# Proiect_TSC_schema.net
KiCad netlist of a schematic drawn in EAGLE
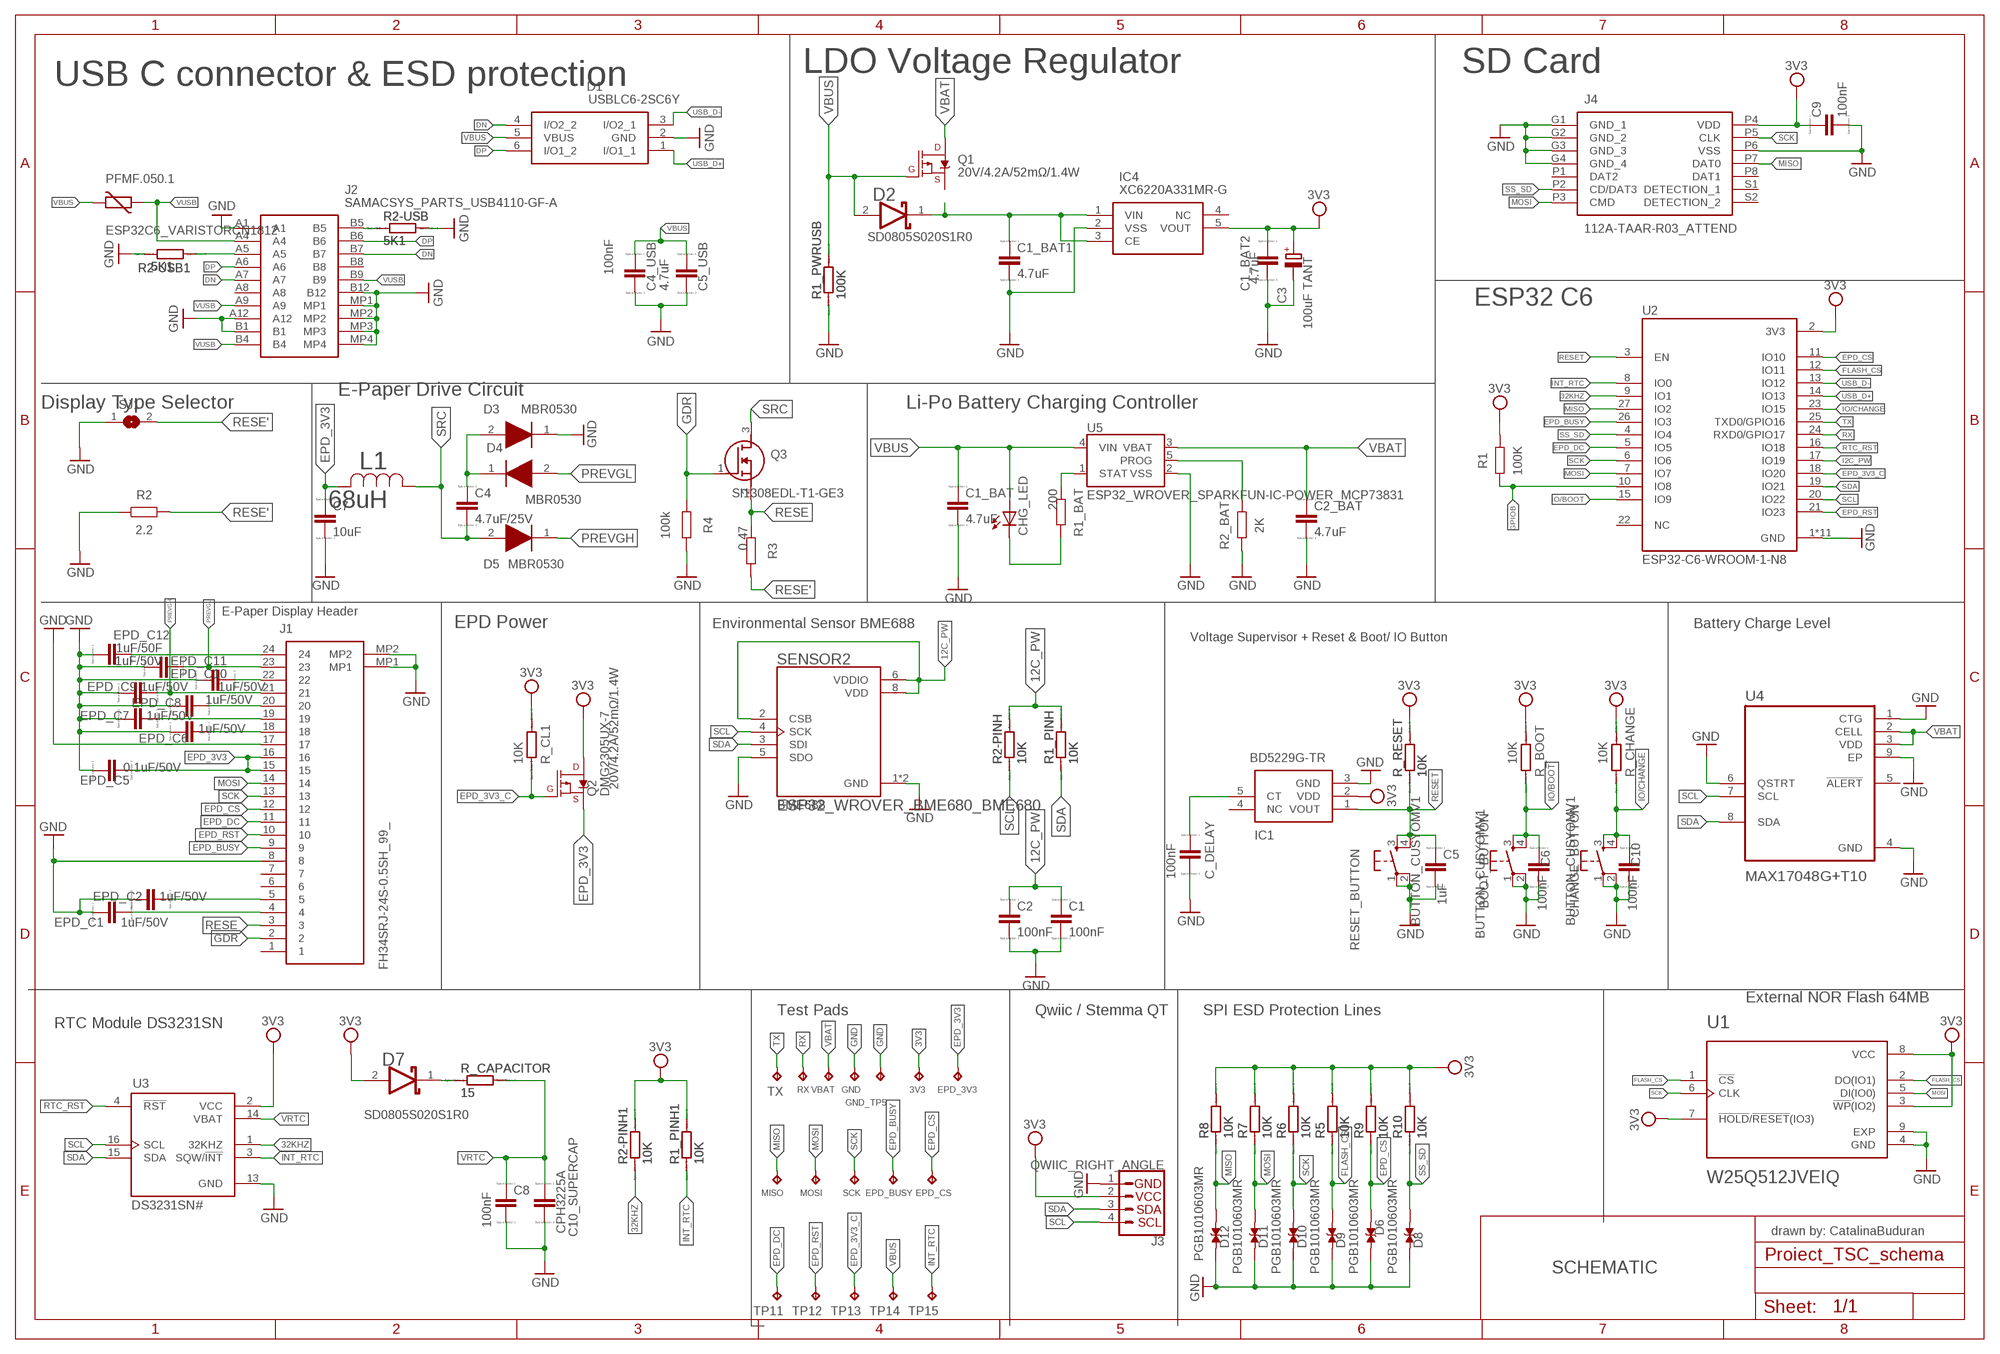
[diagram p0: schematic, sheet 1]

(export (version "E")
  (design (tool "Eeschema 10.0.6"))
  (components
    (comp (ref "3V3")
      (value "TPTP20R")
      (footprint "eagle-import:TP20R")
      (libsource (lib "eagle-import") (part "TPTP20R"))
    )
    (comp (ref "BOOT_BUTTON")
      (value "BUTTON_CUSYOMV1")
      (footprint "eagle-import:MYBUTTON")
      (libsource (lib "eagle-import") (part "BUTTON_CUSYOMV1"))
    )
    (comp (ref "C1")
      (value "100nF")
      (footprint "eagle-import:ESP32_WROVER_EAGLE-LTSPICE_C0402")
      (libsource (lib "eagle-import") (part "ESP32_WROVER_EAGLE-LTSPICE_CC0402"))
    )
    (comp (ref "C1_BAT")
      (value "4.7uF")
      (footprint "eagle-import:ESP32_WROVER_EAGLE-LTSPICE_C0402")
      (libsource (lib "eagle-import") (part "ESP32_WROVER_EAGLE-LTSPICE_CC0402"))
    )
    (comp (ref "C1_BAT1")
      (value "4.7uF")
      (footprint "eagle-import:ESP32_WROVER_EAGLE-LTSPICE_C0402")
      (libsource (lib "eagle-import") (part "ESP32_WROVER_EAGLE-LTSPICE_CC0402"))
    )
    (comp (ref "C1_BAT2")
      (value "4.7uF")
      (footprint "eagle-import:ESP32_WROVER_EAGLE-LTSPICE_C0402")
      (libsource (lib "eagle-import") (part "ESP32_WROVER_EAGLE-LTSPICE_CC0402"))
    )
    (comp (ref "C2")
      (value "100nF")
      (footprint "eagle-import:ESP32_WROVER_EAGLE-LTSPICE_C0402")
      (libsource (lib "eagle-import") (part "ESP32_WROVER_EAGLE-LTSPICE_CC0402"))
    )
    (comp (ref "C2_BAT")
      (value "4.7uF")
      (footprint "eagle-import:ESP32_WROVER_EAGLE-LTSPICE_C0402")
      (libsource (lib "eagle-import") (part "ESP32_WROVER_EAGLE-LTSPICE_CC0402"))
    )
    (comp (ref "C3")
      (value "100uF TANT")
      (footprint "eagle-import:RCL_CT3528")
      (libsource (lib "eagle-import") (part "RCL_CPOL-EUCT3528"))
    )
    (comp (ref "C4")
      (value "4.7uF/25V")
      (footprint "eagle-import:ESP32_WROVER_EAGLE-LTSPICE_C0402")
      (libsource (lib "eagle-import") (part "ESP32_WROVER_EAGLE-LTSPICE_CC0402"))
    )
    (comp (ref "C4_USB")
      (value "100nF")
      (footprint "eagle-import:ESP32_WROVER_EAGLE-LTSPICE_C0402")
      (libsource (lib "eagle-import") (part "ESP32_WROVER_EAGLE-LTSPICE_CC0402"))
    )
    (comp (ref "C5")
      (value "1uF")
      (footprint "eagle-import:EAGLE-LTSPICE_C0402")
      (libsource (lib "eagle-import") (part "EAGLE-LTSPICE_CC0402"))
    )
    (comp (ref "C5_USB")
      (value "4.7uF")
      (footprint "eagle-import:ESP32_WROVER_EAGLE-LTSPICE_C0402")
      (libsource (lib "eagle-import") (part "ESP32_WROVER_EAGLE-LTSPICE_CC0402"))
    )
    (comp (ref "C6")
      (value "100nF")
      (footprint "eagle-import:ESP32_WROVER_EAGLE-LTSPICE_C0402")
      (libsource (lib "eagle-import") (part "ESP32_WROVER_EAGLE-LTSPICE_CC0402"))
    )
    (comp (ref "C7")
      (value "10uF")
      (footprint "eagle-import:ESP32_WROVER_EAGLE-LTSPICE_C0402")
      (libsource (lib "eagle-import") (part "ESP32_WROVER_EAGLE-LTSPICE_CC0402"))
    )
    (comp (ref "C8")
      (value "100nF")
      (footprint "eagle-import:EAGLE-LTSPICE_C0402")
      (libsource (lib "eagle-import") (part "EAGLE-LTSPICE_CC0402"))
    )
    (comp (ref "C9")
      (value "100nF")
      (footprint "eagle-import:ESP32_WROVER_EAGLE-LTSPICE_C0402")
      (libsource (lib "eagle-import") (part "ESP32_WROVER_EAGLE-LTSPICE_CC0402"))
    )
    (comp (ref "C10")
      (value "100nF")
      (footprint "eagle-import:ESP32_WROVER_EAGLE-LTSPICE_C0402")
      (libsource (lib "eagle-import") (part "ESP32_WROVER_EAGLE-LTSPICE_CC0402"))
    )
    (comp (ref "C10_SUPERCAP")
      (value "CPH3225A")
      (footprint "eagle-import:EAGLE-LTSPICE_C0402")
      (libsource (lib "eagle-import") (part "EAGLE-LTSPICE_CC0402"))
    )
    (comp (ref "CHANGE_BUTTON")
      (value "BUTTON_CUSYOMV1")
      (footprint "eagle-import:MYBUTTON")
      (libsource (lib "eagle-import") (part "BUTTON_CUSYOMV1"))
    )
    (comp (ref "CHG_LED")
      (value "ADAFRUIT_LEDCHIP-LED0603")
      (footprint "eagle-import:ADAFRUIT_CHIP-LED0603")
      (libsource (lib "eagle-import") (part "ADAFRUIT_LEDCHIP-LED0603"))
    )
    (comp (ref "C_DELAY")
      (value "100nF")
      (footprint "eagle-import:ESP32_WROVER_EAGLE-LTSPICE_C0402")
      (libsource (lib "eagle-import") (part "ESP32_WROVER_EAGLE-LTSPICE_CC0402"))
    )
    (comp (ref "D1")
      (value "USBLC6-2SC6Y")
      (footprint "eagle-import:SOT95P280X145-6N")
      (fields (field (name "MF") "STMicroelectronics"))
      (libsource (lib "eagle-import") (part "USBLC6-2SC6Y"))
    )
    (comp (ref "D2")
      (value "ESP32_WROVER_AVX---SD0805S020S1R0_AVX_SD0805S020S1R0_0_0AVX_SD0805S020S1R0_0_0")
      (footprint "eagle-import:ESP32_WROVER_AVX---SD0805S020S1R0_AVX_SD0805S020S1R0_0")
      (fields
        (field (name "DIGIKEY_PART_NUMBER") "478-7800-1-ND")
        (field (name "MF") "AVX")
        (field (name "MOUSER_PART_NUMBER") "581-SD0805S020S1R0")
      )
      (libsource (lib "eagle-import") (part "ESP32_WROVER_AVX---SD0805S020S1R0_AVX_SD0805S020S1R0_0_0AVX_SD0805S020S1R0_0_0"))
    )
    (comp (ref "D3")
      (value "MBR0530")
      (footprint "eagle-import:SOD3716X135N")
      (fields (field (name "MF") "ON Semiconductor"))
      (libsource (lib "eagle-import") (part "MBR0530"))
    )
    (comp (ref "D4")
      (value "MBR0530")
      (footprint "eagle-import:SOD3716X135N")
      (fields (field (name "MF") "ON Semiconductor"))
      (libsource (lib "eagle-import") (part "MBR0530"))
    )
    (comp (ref "D5")
      (value "MBR0530")
      (footprint "eagle-import:SOD3716X135N")
      (fields (field (name "MF") "ON Semiconductor"))
      (libsource (lib "eagle-import") (part "MBR0530"))
    )
    (comp (ref "D6")
      (value "PGB1010603MR")
      (footprint "eagle-import:DIOC1608X36N")
      (fields (field (name "MF") "Littelfuse Inc."))
      (libsource (lib "eagle-import") (part "PGB1010603MR"))
    )
    (comp (ref "D7")
      (value "ESP32_WROVER_AVX---SD0805S020S1R0_AVX_SD0805S020S1R0_0_0AVX_SD0805S020S1R0_0_0")
      (footprint "eagle-import:ESP32_WROVER_AVX---SD0805S020S1R0_AVX_SD0805S020S1R0_0")
      (fields
        (field (name "DIGIKEY_PART_NUMBER") "478-7800-1-ND")
        (field (name "MF") "AVX")
        (field (name "MOUSER_PART_NUMBER") "581-SD0805S020S1R0")
      )
      (libsource (lib "eagle-import") (part "ESP32_WROVER_AVX---SD0805S020S1R0_AVX_SD0805S020S1R0_0_0AVX_SD0805S020S1R0_0_0"))
    )
    (comp (ref "D8")
      (value "PGB1010603MR")
      (footprint "eagle-import:DIOC1608X36N")
      (fields (field (name "MF") "Littelfuse Inc."))
      (libsource (lib "eagle-import") (part "PGB1010603MR"))
    )
    (comp (ref "D9")
      (value "PGB1010603MR")
      (footprint "eagle-import:DIOC1608X36N")
      (fields (field (name "MF") "Littelfuse Inc."))
      (libsource (lib "eagle-import") (part "PGB1010603MR"))
    )
    (comp (ref "D10")
      (value "PGB1010603MR")
      (footprint "eagle-import:DIOC1608X36N")
      (fields (field (name "MF") "Littelfuse Inc."))
      (libsource (lib "eagle-import") (part "PGB1010603MR"))
    )
    (comp (ref "D11")
      (value "PGB1010603MR")
      (footprint "eagle-import:DIOC1608X36N")
      (fields (field (name "MF") "Littelfuse Inc."))
      (libsource (lib "eagle-import") (part "PGB1010603MR"))
    )
    (comp (ref "D12")
      (value "PGB1010603MR")
      (footprint "eagle-import:DIOC1608X36N")
      (fields (field (name "MF") "Littelfuse Inc."))
      (libsource (lib "eagle-import") (part "PGB1010603MR"))
    )
    (comp (ref "EPD_3V3")
      (value "TPTP20R")
      (footprint "eagle-import:TP20R")
      (libsource (lib "eagle-import") (part "TPTP20R"))
    )
    (comp (ref "EPD_BUSY")
      (value "TPTP20R")
      (footprint "eagle-import:TP20R")
      (libsource (lib "eagle-import") (part "TPTP20R"))
    )
    (comp (ref "EPD_C1")
      (value "1uF/50V")
      (footprint "eagle-import:ESP32_WROVER_EAGLE-LTSPICE_C0402")
      (libsource (lib "eagle-import") (part "ESP32_WROVER_EAGLE-LTSPICE_CC0402"))
    )
    (comp (ref "EPD_C2")
      (value "1uF/50V")
      (footprint "eagle-import:ESP32_WROVER_EAGLE-LTSPICE_C0402")
      (libsource (lib "eagle-import") (part "ESP32_WROVER_EAGLE-LTSPICE_CC0402"))
    )
    (comp (ref "EPD_C5")
      (value "0.1uF/50V")
      (footprint "eagle-import:ESP32_WROVER_EAGLE-LTSPICE_C0402")
      (libsource (lib "eagle-import") (part "ESP32_WROVER_EAGLE-LTSPICE_CC0402"))
    )
    (comp (ref "EPD_C6")
      (value "1uF/50V")
      (footprint "eagle-import:ESP32_WROVER_EAGLE-LTSPICE_C0402")
      (libsource (lib "eagle-import") (part "ESP32_WROVER_EAGLE-LTSPICE_CC0402"))
    )
    (comp (ref "EPD_C7")
      (value "1uF/50V")
      (footprint "eagle-import:ESP32_WROVER_EAGLE-LTSPICE_C0402")
      (libsource (lib "eagle-import") (part "ESP32_WROVER_EAGLE-LTSPICE_CC0402"))
    )
    (comp (ref "EPD_C8")
      (value "1uF/50V")
      (footprint "eagle-import:ESP32_WROVER_EAGLE-LTSPICE_C0402")
      (libsource (lib "eagle-import") (part "ESP32_WROVER_EAGLE-LTSPICE_CC0402"))
    )
    (comp (ref "EPD_C9")
      (value "1uF/50V")
      (footprint "eagle-import:ESP32_WROVER_EAGLE-LTSPICE_C0402")
      (libsource (lib "eagle-import") (part "ESP32_WROVER_EAGLE-LTSPICE_CC0402"))
    )
    (comp (ref "EPD_C10")
      (value "1uF/50V")
      (footprint "eagle-import:ESP32_WROVER_EAGLE-LTSPICE_C0402")
      (libsource (lib "eagle-import") (part "ESP32_WROVER_EAGLE-LTSPICE_CC0402"))
    )
    (comp (ref "EPD_C11")
      (value "1uF/50V")
      (footprint "eagle-import:ESP32_WROVER_EAGLE-LTSPICE_C0402")
      (libsource (lib "eagle-import") (part "ESP32_WROVER_EAGLE-LTSPICE_CC0402"))
    )
    (comp (ref "EPD_C12")
      (value "1uF/50F")
      (footprint "eagle-import:ESP32_WROVER_EAGLE-LTSPICE_C0402")
      (libsource (lib "eagle-import") (part "ESP32_WROVER_EAGLE-LTSPICE_CC0402"))
    )
    (comp (ref "EPD_CS")
      (value "TPTP20R")
      (footprint "eagle-import:TP20R")
      (libsource (lib "eagle-import") (part "TPTP20R"))
    )
    (comp (ref "GND")
      (value "TPTP20R")
      (footprint "eagle-import:TP20R")
      (libsource (lib "eagle-import") (part "TPTP20R"))
    )
    (comp (ref "GND_TP5")
      (value "TPTP20R")
      (footprint "eagle-import:TP20R")
      (libsource (lib "eagle-import") (part "TPTP20R"))
    )
    (comp (ref "IC1")
      (value "BD5229G-TR")
      (footprint "eagle-import:SOT95P280X125-5N")
      (fields (field (name "MOUSER_PART_NUMBER") "755-BD5229G-TR"))
      (libsource (lib "eagle-import") (part "BD5229G-TR"))
    )
    (comp (ref "IC4")
      (value "XC6220A331MR-G")
      (footprint "eagle-import:SOT95P280X120-5N")
      (fields (field (name "MOUSER_PART_NUMBER") "865-XC6220A331MR-G"))
      (libsource (lib "eagle-import") (part "XC6220A331MR-G"))
    )
    (comp (ref "J1")
      (value "FH34SRJ-24S-0.5SH_99_")
      (footprint "eagle-import:FH34SRJ24S05SH99")
      (fields
        (field (name "MANUFACTURER_PART_NUMBER") "FH34SRJ-24S-0.5SH(99)")
        (field (name "MOUSER_PART_NUMBER") "798-FH34SRJ24S05SH99")
      )
      (libsource (lib "eagle-import") (part "FH34SRJ-24S-0.5SH_99_"))
    )
    (comp (ref "J2")
      (value "SAMACSYS_PARTS_USB4110-GF-A")
      (footprint "eagle-import:SAMACSYS_PARTS_USB4110GFA")
      (fields
        (field (name "MANUFACTURER_PART_NUMBER") "USB4110-GF-A")
        (field (name "MOUSER_PART_NUMBER") "640-USB4110-GF-A")
      )
      (libsource (lib "eagle-import") (part "SAMACSYS_PARTS_USB4110-GF-A"))
    )
    (comp (ref "J3")
      (value "QWIIC_RIGHT_ANGLE")
      (footprint "eagle-import:JST04_1MM_RA")
      (libsource (lib "eagle-import") (part "QWIIC_CONNECTORJS-1MM"))
    )
    (comp (ref "J4")
      (value "112A-TAAR-R03_ATTEND")
      (footprint "eagle-import:112ATAARR03ATTEND")
      (fields (field (name "MANUFACTURER_PART_NUMBER") "112A-TAAR-R03 ATTEND"))
      (libsource (lib "eagle-import") (part "112A-TAAR-R03_ATTEND"))
    )
    (comp (ref "L1")
      (value "68uH")
      (footprint "eagle-import:IND_4828-WE-TPC_WRE")
      (fields
        (field (name "MANUFACTURER_PART_NUMBER") "744043680")
        (field (name "COPYRIGHT") "Copyright (C) 2024 Ultra Librarian. All rights reserved.")
      )
      (libsource (lib "eagle-import") (part "744043680IND_4828-WE-TPC_WRE"))
    )
    (comp (ref "MISO")
      (value "TPTP20R")
      (footprint "eagle-import:TP20R")
      (libsource (lib "eagle-import") (part "TPTP20R"))
    )
    (comp (ref "MOSI")
      (value "TPTP20R")
      (footprint "eagle-import:TP20R")
      (libsource (lib "eagle-import") (part "TPTP20R"))
    )
    (comp (ref "PFMF.050.1")
      (value "ESP32C6_VARISTORCN1812")
      (footprint "eagle-import:ESP32C6_VARISTOR_CT_CN1812")
      (libsource (lib "eagle-import") (part "ESP32C6_VARISTORCN1812"))
    )
    (comp (ref "Q1")
      (value "20V/4.2A/52mΩ/1.4W")
      (footprint "eagle-import:ESP32_WROVER_SPARKFUN-DISCRETESEMI_SOT23-3")
      (libsource (lib "eagle-import") (part "ESP32_WROVER_SPARKFUN-DISCRETESEMI_MOSFET_PCH-DMG2305UX-7"))
    )
    (comp (ref "Q2")
      (value "20V/4.2A/52mΩ/1.4W")
      (footprint "eagle-import:ESP32_WROVER_SPARKFUN-DISCRETESEMI_SOT23-3")
      (libsource (lib "eagle-import") (part "ESP32_WROVER_SPARKFUN-DISCRETESEMI_MOSFET_PCH-DMG2305UX-7"))
    )
    (comp (ref "Q3")
      (value "SI1308EDL-T1-GE3")
      (footprint "eagle-import:SOT65P210X110-3N")
      (fields (field (name "MF") "Vishay Siliconix"))
      (libsource (lib "eagle-import") (part "SI1308EDL-T1-GE3"))
    )
    (comp (ref "R1")
      (value "100K")
      (footprint "eagle-import:RESC1005X40")
      (libsource (lib "eagle-import") (part "RCHIP-0402(1005-METRIC)_"))
    )
    (comp (ref "R1_BAT")
      (value "200")
      (footprint "eagle-import:RESC1005X40")
      (libsource (lib "eagle-import") (part "RCHIP-0402(1005-METRIC)_"))
    )
    (comp (ref "R1_PINH")
      (value "10K")
      (footprint "eagle-import:ESP32_WROVER_EAGLE-LTSPICE_R0402")
      (libsource (lib "eagle-import") (part "ESP32_WROVER_EAGLE-LTSPICE_RR0402"))
    )
    (comp (ref "R1_PINH1")
      (value "10K")
      (footprint "eagle-import:ESP32_WROVER_EAGLE-LTSPICE_R0402")
      (libsource (lib "eagle-import") (part "ESP32_WROVER_EAGLE-LTSPICE_RR0402"))
    )
    (comp (ref "R1_PWRUSB")
      (value "100K")
      (footprint "eagle-import:ESP32_WROVER_EAGLE-LTSPICE_R0402")
      (libsource (lib "eagle-import") (part "ESP32_WROVER_EAGLE-LTSPICE_RR0402"))
    )
    (comp (ref "R2")
      (value "2.2")
      (footprint "eagle-import:RESC1005X40")
      (libsource (lib "eagle-import") (part "RCHIP-0402(1005-METRIC)_"))
    )
    (comp (ref "R2-PINH")
      (value "10K")
      (footprint "eagle-import:ESP32_WROVER_EAGLE-LTSPICE_R0402")
      (libsource (lib "eagle-import") (part "ESP32_WROVER_EAGLE-LTSPICE_RR0402"))
    )
    (comp (ref "R2-PINH1")
      (value "10K")
      (footprint "eagle-import:ESP32_WROVER_EAGLE-LTSPICE_R0402")
      (libsource (lib "eagle-import") (part "ESP32_WROVER_EAGLE-LTSPICE_RR0402"))
    )
    (comp (ref "R2-USB")
      (value "5K1")
      (footprint "eagle-import:ESP32_WROVER_EAGLE-LTSPICE_R0402")
      (libsource (lib "eagle-import") (part "ESP32_WROVER_EAGLE-LTSPICE_RR0402"))
    )
    (comp (ref "R2-USB1")
      (value "5K1")
      (footprint "eagle-import:ESP32_WROVER_EAGLE-LTSPICE_R0402")
      (libsource (lib "eagle-import") (part "ESP32_WROVER_EAGLE-LTSPICE_RR0402"))
    )
    (comp (ref "R2_BAT")
      (value "2K")
      (footprint "eagle-import:RESC1005X40")
      (libsource (lib "eagle-import") (part "RCHIP-0402(1005-METRIC)_"))
    )
    (comp (ref "R3")
      (value "0.47")
      (footprint "eagle-import:RESC1005X40")
      (libsource (lib "eagle-import") (part "RCHIP-0402(1005-METRIC)_"))
    )
    (comp (ref "R4")
      (value "100k")
      (footprint "eagle-import:RESC1005X40")
      (libsource (lib "eagle-import") (part "RCHIP-0402(1005-METRIC)_"))
    )
    (comp (ref "R5")
      (value "10K")
      (footprint "eagle-import:ESP32_WROVER_EAGLE-LTSPICE_R0402")
      (libsource (lib "eagle-import") (part "ESP32_WROVER_EAGLE-LTSPICE_RR0402"))
    )
    (comp (ref "R6")
      (value "10K")
      (footprint "eagle-import:ESP32_WROVER_EAGLE-LTSPICE_R0402")
      (libsource (lib "eagle-import") (part "ESP32_WROVER_EAGLE-LTSPICE_RR0402"))
    )
    (comp (ref "R7")
      (value "10K")
      (footprint "eagle-import:ESP32_WROVER_EAGLE-LTSPICE_R0402")
      (libsource (lib "eagle-import") (part "ESP32_WROVER_EAGLE-LTSPICE_RR0402"))
    )
    (comp (ref "R8")
      (value "10K")
      (footprint "eagle-import:ESP32_WROVER_EAGLE-LTSPICE_R0402")
      (libsource (lib "eagle-import") (part "ESP32_WROVER_EAGLE-LTSPICE_RR0402"))
    )
    (comp (ref "R9")
      (value "10K")
      (footprint "eagle-import:ESP32_WROVER_EAGLE-LTSPICE_R0402")
      (libsource (lib "eagle-import") (part "ESP32_WROVER_EAGLE-LTSPICE_RR0402"))
    )
    (comp (ref "R10")
      (value "10K")
      (footprint "eagle-import:ESP32_WROVER_EAGLE-LTSPICE_R0402")
      (libsource (lib "eagle-import") (part "ESP32_WROVER_EAGLE-LTSPICE_RR0402"))
    )
    (comp (ref "RESET_BUTTON")
      (value "BUTTON_CUSYOMV1")
      (footprint "eagle-import:MYBUTTON")
      (libsource (lib "eagle-import") (part "BUTTON_CUSYOMV1"))
    )
    (comp (ref "RX")
      (value "TPTP20R")
      (footprint "eagle-import:TP20R")
      (libsource (lib "eagle-import") (part "TPTP20R"))
    )
    (comp (ref "R_BOOT")
      (value "10K")
      (footprint "eagle-import:ESP32_WROVER_EAGLE-LTSPICE_R0402")
      (libsource (lib "eagle-import") (part "ESP32_WROVER_EAGLE-LTSPICE_RR0402"))
    )
    (comp (ref "R_CAPACITOR")
      (value "15")
      (footprint "eagle-import:ESP32_WROVER_EAGLE-LTSPICE_R0402")
      (libsource (lib "eagle-import") (part "ESP32_WROVER_EAGLE-LTSPICE_RR0402"))
    )
    (comp (ref "R_CHANGE")
      (value "10K")
      (footprint "eagle-import:ESP32_WROVER_EAGLE-LTSPICE_R0402")
      (libsource (lib "eagle-import") (part "ESP32_WROVER_EAGLE-LTSPICE_RR0402"))
    )
    (comp (ref "R_CL1")
      (value "10K")
      (footprint "eagle-import:ESP32_WROVER_EAGLE-LTSPICE_R0402")
      (libsource (lib "eagle-import") (part "ESP32_WROVER_EAGLE-LTSPICE_RR0402"))
    )
    (comp (ref "R_RESET")
      (value "10K")
      (footprint "eagle-import:ESP32_WROVER_EAGLE-LTSPICE_R0402")
      (libsource (lib "eagle-import") (part "ESP32_WROVER_EAGLE-LTSPICE_RR0402"))
    )
    (comp (ref "SCK")
      (value "TPTP20R")
      (footprint "eagle-import:TP20R")
      (libsource (lib "eagle-import") (part "TPTP20R"))
    )
    (comp (ref "SENSOR2")
      (value "ESP32_WROVER_BME680_BME680")
      (footprint "eagle-import:ESP32_WROVER_BME680_PSON80P300X300X100-8N")
      (fields (field (name "MF") "Bosch Sensortec") (field (name "MP") "BME680"))
      (libsource (lib "eagle-import") (part "ESP32_WROVER_BME680_BME680"))
    )
    (comp (ref "SJ1") (value "SJ") (footprint "eagle-import:SJ") (libsource (lib "eagle-import") (part "SJ")))
    (comp (ref "TP11")
      (value "TPTP20R")
      (footprint "eagle-import:TP20R")
      (libsource (lib "eagle-import") (part "TPTP20R"))
    )
    (comp (ref "TP12")
      (value "TPTP20R")
      (footprint "eagle-import:TP20R")
      (libsource (lib "eagle-import") (part "TPTP20R"))
    )
    (comp (ref "TP13")
      (value "TPTP20R")
      (footprint "eagle-import:TP20R")
      (libsource (lib "eagle-import") (part "TPTP20R"))
    )
    (comp (ref "TP14")
      (value "TPTP20R")
      (footprint "eagle-import:TP20R")
      (libsource (lib "eagle-import") (part "TPTP20R"))
    )
    (comp (ref "TP15")
      (value "TPTP20R")
      (footprint "eagle-import:TP20R")
      (libsource (lib "eagle-import") (part "TPTP20R"))
    )
    (comp (ref "TX")
      (value "TPTP20R")
      (footprint "eagle-import:TP20R")
      (libsource (lib "eagle-import") (part "TPTP20R"))
    )
    (comp (ref "U1")
      (value "W25Q512JVEIQ")
      (footprint "eagle-import:SON127P600X800X80-9N")
      (fields (field (name "MF") "Winbond Electronics"))
      (libsource (lib "eagle-import") (part "W25Q512JVEIQ"))
    )
    (comp (ref "U2")
      (value "ESP32-C6-WROOM-1-N8")
      (footprint "eagle-import:XCVR_ESP32-C6-WROOM-1-N8")
      (fields (field (name "MF") "Espressif Systems"))
      (libsource (lib "eagle-import") (part "ESP32-C6-WROOM-1-N8"))
    )
    (comp (ref "U3")
      (value "DS3231SN#")
      (footprint "eagle-import:SOIC127P1032X265-16N")
      (fields (field (name "MF") "Analog Devices"))
      (libsource (lib "eagle-import") (part "DS3231SN#"))
    )
    (comp (ref "U4")
      (value "MAX17048G+T10")
      (footprint "eagle-import:SON50P200X200X80-9N")
      (fields (field (name "MF") "Analog Devices"))
      (libsource (lib "eagle-import") (part "MAX17048G+T10"))
    )
    (comp (ref "U5")
      (value "ESP32_WROVER_SPARKFUN-IC-POWER_MCP73831")
      (footprint "eagle-import:ESP32_WROVER_SPARKFUN-IC-POWER_SOT23-5")
      (libsource (lib "eagle-import") (part "ESP32_WROVER_SPARKFUN-IC-POWER_MCP73831"))
    )
    (comp (ref "VBAT")
      (value "TPTP20R")
      (footprint "eagle-import:TP20R")
      (libsource (lib "eagle-import") (part "TPTP20R"))
    )
  )
  (nets
    (net (code "1") (name "3V3") (class "Default")
      (node (ref "3V3") (pin "TP") (pinfunction "TP_TP") (pintype "input"))
      (node (ref "C1_BAT2") (pin "1") (pinfunction "1_1") (pintype "passive"))
      (node (ref "C3") (pin "+") (pinfunction "+_+") (pintype "passive"))
      (node (ref "C9") (pin "1") (pinfunction "1_1") (pintype "passive"))
      (node (ref "D7") (pin "2") (pinfunction "ANODE_2") (pintype "bidirectional"))
      (node (ref "IC1") (pin "2") (pinfunction "VDD_2") (pintype "bidirectional"))
      (node (ref "IC4") (pin "5") (pinfunction "VOUT_5") (pintype "bidirectional"))
      (node (ref "J3") (pin "2") (pinfunction "2_2") (pintype "power_in"))
      (node (ref "J4") (pin "P4") (pinfunction "VDD_P4") (pintype "bidirectional"))
      (node (ref "Q2") (pin "3") (pinfunction "D_3") (pintype "bidirectional"))
      (node (ref "R1") (pin "2") (pinfunction "2_2") (pintype "passive"))
      (node (ref "R10") (pin "2") (pinfunction "2_2") (pintype "passive"))
      (node (ref "R1_PINH1") (pin "2") (pinfunction "2_2") (pintype "passive"))
      (node (ref "R2-PINH1") (pin "2") (pinfunction "2_2") (pintype "passive"))
      (node (ref "R5") (pin "2") (pinfunction "2_2") (pintype "passive"))
      (node (ref "R6") (pin "2") (pinfunction "2_2") (pintype "passive"))
      (node (ref "R7") (pin "2") (pinfunction "2_2") (pintype "passive"))
      (node (ref "R8") (pin "2") (pinfunction "2_2") (pintype "passive"))
      (node (ref "R9") (pin "2") (pinfunction "2_2") (pintype "passive"))
      (node (ref "R_BOOT") (pin "2") (pinfunction "2_2") (pintype "passive"))
      (node (ref "R_CHANGE") (pin "2") (pinfunction "2_2") (pintype "passive"))
      (node (ref "R_CL1") (pin "2") (pinfunction "2_2") (pintype "passive"))
      (node (ref "R_RESET") (pin "2") (pinfunction "2_2") (pintype "passive"))
      (node (ref "U1") (pin "3") (pinfunction "~{WP}(IO2)_3") (pintype "bidirectional"))
      (node (ref "U1") (pin "7") (pinfunction "~{HOLD}/~{RESET}(IO3)_7") (pintype "bidirectional"))
      (node (ref "U1") (pin "8") (pinfunction "VCC_8") (pintype "power_in"))
      (node (ref "U2") (pin "2") (pinfunction "3V3_2") (pintype "power_in"))
      (node (ref "U3") (pin "2") (pinfunction "VCC_2") (pintype "power_in"))
    )
    (net (code "2") (name "12C_PW") (class "Default")
      (node (ref "C1") (pin "1") (pinfunction "1_1") (pintype "passive"))
      (node (ref "C2") (pin "1") (pinfunction "1_1") (pintype "passive"))
      (node (ref "R1_PINH") (pin "2") (pinfunction "2_2") (pintype "passive"))
      (node (ref "R2-PINH") (pin "2") (pinfunction "2_2") (pintype "passive"))
      (node (ref "SENSOR2") (pin "2") (pinfunction "CSB_2") (pintype "input"))
      (node (ref "SENSOR2") (pin "6") (pinfunction "VDDIO_6") (pintype "power_in"))
      (node (ref "SENSOR2") (pin "8") (pinfunction "VDD_8") (pintype "power_in"))
    )
    (net (code "3") (name "32KHZ") (class "Default")
      (node (ref "R2-PINH1") (pin "1") (pinfunction "1_1") (pintype "passive"))
      (node (ref "U2") (pin "9") (pinfunction "IO1_9") (pintype "bidirectional"))
      (node (ref "U3") (pin "1") (pinfunction "32KHZ_1") (pintype "output"))
    )
    (net (code "4") (name "DN") (class "Default")
      (node (ref "D1") (pin "4") (pinfunction "I/O2_2_4") (pintype "bidirectional"))
      (node (ref "J2") (pin "A7") (pinfunction "A7_A7") (pintype "bidirectional"))
      (node (ref "J2") (pin "B7") (pinfunction "B7_B7") (pintype "bidirectional"))
    )
    (net (code "5") (name "DP") (class "Default")
      (node (ref "D1") (pin "6") (pinfunction "I/O1_2_6") (pintype "bidirectional"))
      (node (ref "J2") (pin "A6") (pinfunction "A6_A6") (pintype "bidirectional"))
      (node (ref "J2") (pin "B6") (pinfunction "B6_B6") (pintype "bidirectional"))
    )
    (net (code "6") (name "EPD_3V3") (class "Default")
      (node (ref "C7") (pin "1") (pinfunction "1_1") (pintype "passive"))
      (node (ref "EPD_3V3") (pin "TP") (pinfunction "TP_TP") (pintype "input"))
      (node (ref "EPD_C5") (pin "2") (pinfunction "2_2") (pintype "passive"))
      (node (ref "J1") (pin "15") (pinfunction "15_15") (pintype "bidirectional"))
      (node (ref "J1") (pin "16") (pinfunction "16_16") (pintype "bidirectional"))
      (node (ref "L1") (pin "2") (pinfunction "2_2") (pintype "passive"))
      (node (ref "Q2") (pin "2") (pinfunction "S_2") (pintype "bidirectional"))
    )
    (net (code "7") (name "EPD_3V3_C") (class "Default")
      (node (ref "Q2") (pin "1") (pinfunction "G_1") (pintype "bidirectional"))
      (node (ref "R_CL1") (pin "1") (pinfunction "1_1") (pintype "passive"))
      (node (ref "TP13") (pin "TP") (pinfunction "TP_TP") (pintype "input"))
      (node (ref "U2") (pin "18") (pinfunction "IO20_18") (pintype "bidirectional"))
    )
    (net (code "8") (name "EPD_BUSY") (class "Default")
      (node (ref "EPD_BUSY") (pin "TP") (pinfunction "TP_TP") (pintype "input"))
      (node (ref "J1") (pin "9") (pinfunction "9_9") (pintype "bidirectional"))
      (node (ref "U2") (pin "26") (pinfunction "IO3_26") (pintype "bidirectional"))
    )
    (net (code "9") (name "EPD_CS") (class "Default")
      (node (ref "D6") (pin "2") (pinfunction "2_2") (pintype "passive"))
      (node (ref "EPD_CS") (pin "TP") (pinfunction "TP_TP") (pintype "input"))
      (node (ref "J1") (pin "12") (pinfunction "12_12") (pintype "bidirectional"))
      (node (ref "R9") (pin "1") (pinfunction "1_1") (pintype "passive"))
      (node (ref "U2") (pin "11") (pinfunction "IO10_11") (pintype "bidirectional"))
    )
    (net (code "10") (name "EPD_DC") (class "Default")
      (node (ref "J1") (pin "11") (pinfunction "11_11") (pintype "bidirectional"))
      (node (ref "TP11") (pin "TP") (pinfunction "TP_TP") (pintype "input"))
      (node (ref "U2") (pin "5") (pinfunction "IO5_5") (pintype "bidirectional"))
    )
    (net (code "11") (name "EPD_RST") (class "Default")
      (node (ref "J1") (pin "10") (pinfunction "10_10") (pintype "bidirectional"))
      (node (ref "TP12") (pin "TP") (pinfunction "TP_TP") (pintype "input"))
      (node (ref "U2") (pin "21") (pinfunction "IO23_21") (pintype "bidirectional"))
    )
    (net (code "12") (name "FLASH_CS") (class "Default")
      (node (ref "D9") (pin "2") (pinfunction "2_2") (pintype "passive"))
      (node (ref "R5") (pin "1") (pinfunction "1_1") (pintype "passive"))
      (node (ref "U1") (pin "1") (pinfunction "~{CS}_1") (pintype "input"))
      (node (ref "U2") (pin "12") (pinfunction "IO11_12") (pintype "bidirectional"))
    )
    (net (code "13") (name "GDR") (class "Default")
      (node (ref "J1") (pin "2") (pinfunction "2_2") (pintype "bidirectional"))
      (node (ref "Q3") (pin "1") (pinfunction "G_1") (pintype "bidirectional"))
      (node (ref "R4") (pin "2") (pinfunction "2_2") (pintype "passive"))
    )
    (net (code "14") (name "GND") (class "Default")
      (node (ref "BOOT_BUTTON") (pin "1") (pinfunction "1_1") (pintype "passive"))
      (node (ref "BOOT_BUTTON") (pin "2") (pinfunction "2_2") (pintype "passive"))
      (node (ref "C1") (pin "2") (pinfunction "2_2") (pintype "passive"))
      (node (ref "C10") (pin "2") (pinfunction "2_2") (pintype "passive"))
      (node (ref "C10_SUPERCAP") (pin "2") (pinfunction "2_2") (pintype "passive"))
      (node (ref "C1_BAT") (pin "2") (pinfunction "2_2") (pintype "passive"))
      (node (ref "C1_BAT1") (pin "2") (pinfunction "2_2") (pintype "passive"))
      (node (ref "C1_BAT2") (pin "2") (pinfunction "2_2") (pintype "passive"))
      (node (ref "C2") (pin "2") (pinfunction "2_2") (pintype "passive"))
      (node (ref "C2_BAT") (pin "2") (pinfunction "2_2") (pintype "passive"))
      (node (ref "C3") (pin "-") (pinfunction "-_-") (pintype "passive"))
      (node (ref "C4_USB") (pin "2") (pinfunction "2_2") (pintype "passive"))
      (node (ref "C5") (pin "2") (pinfunction "2_2") (pintype "passive"))
      (node (ref "C5_USB") (pin "2") (pinfunction "2_2") (pintype "passive"))
      (node (ref "C6") (pin "2") (pinfunction "2_2") (pintype "passive"))
      (node (ref "C7") (pin "2") (pinfunction "2_2") (pintype "passive"))
      (node (ref "C8") (pin "2") (pinfunction "2_2") (pintype "passive"))
      (node (ref "C9") (pin "2") (pinfunction "2_2") (pintype "passive"))
      (node (ref "CHANGE_BUTTON") (pin "1") (pinfunction "1_1") (pintype "passive"))
      (node (ref "CHANGE_BUTTON") (pin "2") (pinfunction "2_2") (pintype "passive"))
      (node (ref "C_DELAY") (pin "2") (pinfunction "2_2") (pintype "passive"))
      (node (ref "D1") (pin "2") (pinfunction "GND_2") (pintype "bidirectional"))
      (node (ref "D10") (pin "1") (pinfunction "1_1") (pintype "passive"))
      (node (ref "D11") (pin "1") (pinfunction "1_1") (pintype "passive"))
      (node (ref "D12") (pin "1") (pinfunction "1_1") (pintype "passive"))
      (node (ref "D3") (pin "1") (pinfunction "K_1") (pintype "bidirectional"))
      (node (ref "D6") (pin "1") (pinfunction "1_1") (pintype "passive"))
      (node (ref "D8") (pin "1") (pinfunction "1_1") (pintype "passive"))
      (node (ref "D9") (pin "1") (pinfunction "1_1") (pintype "passive"))
      (node (ref "EPD_C1") (pin "1") (pinfunction "1_1") (pintype "passive"))
      (node (ref "EPD_C10") (pin "1") (pinfunction "1_1") (pintype "passive"))
      (node (ref "EPD_C11") (pin "1") (pinfunction "1_1") (pintype "passive"))
      (node (ref "EPD_C12") (pin "1") (pinfunction "1_1") (pintype "passive"))
      (node (ref "EPD_C2") (pin "1") (pinfunction "1_1") (pintype "passive"))
      (node (ref "EPD_C5") (pin "1") (pinfunction "1_1") (pintype "passive"))
      (node (ref "EPD_C6") (pin "1") (pinfunction "1_1") (pintype "passive"))
      (node (ref "EPD_C7") (pin "1") (pinfunction "1_1") (pintype "passive"))
      (node (ref "EPD_C8") (pin "1") (pinfunction "1_1") (pintype "passive"))
      (node (ref "EPD_C9") (pin "1") (pinfunction "1_1") (pintype "passive"))
      (node (ref "GND") (pin "TP") (pinfunction "TP_TP") (pintype "input"))
      (node (ref "GND_TP5") (pin "TP") (pinfunction "TP_TP") (pintype "input"))
      (node (ref "IC1") (pin "3") (pinfunction "GND_3") (pintype "bidirectional"))
      (node (ref "IC4") (pin "2") (pinfunction "VSS_2") (pintype "bidirectional"))
      (node (ref "J1") (pin "17") (pinfunction "17_17") (pintype "bidirectional"))
      (node (ref "J1") (pin "8") (pinfunction "8_8") (pintype "bidirectional"))
      (node (ref "J1") (pin "MP1") (pinfunction "MP1_MP1") (pintype "bidirectional"))
      (node (ref "J1") (pin "MP2") (pinfunction "MP2_MP2") (pintype "bidirectional"))
      (node (ref "J2") (pin "A1") (pinfunction "A1_A1") (pintype "bidirectional"))
      (node (ref "J2") (pin "A12") (pinfunction "A12_A12") (pintype "bidirectional"))
      (node (ref "J2") (pin "B1") (pinfunction "B1_B1") (pintype "bidirectional"))
      (node (ref "J2") (pin "B12") (pinfunction "B12_B12") (pintype "bidirectional"))
      (node (ref "J2") (pin "MP1") (pinfunction "MP1_MP1") (pintype "bidirectional"))
      (node (ref "J2") (pin "MP2") (pinfunction "MP2_MP2") (pintype "bidirectional"))
      (node (ref "J2") (pin "MP3") (pinfunction "MP3_MP3") (pintype "bidirectional"))
      (node (ref "J2") (pin "MP4") (pinfunction "MP4_MP4") (pintype "bidirectional"))
      (node (ref "J3") (pin "1") (pinfunction "1_1") (pintype "power_in"))
      (node (ref "J4") (pin "G1") (pinfunction "GND_1_G1") (pintype "bidirectional"))
      (node (ref "J4") (pin "G2") (pinfunction "GND_2_G2") (pintype "bidirectional"))
      (node (ref "J4") (pin "G3") (pinfunction "GND_3_G3") (pintype "bidirectional"))
      (node (ref "J4") (pin "G4") (pinfunction "GND_4_G4") (pintype "bidirectional"))
      (node (ref "J4") (pin "P6") (pinfunction "VSS_P6") (pintype "bidirectional"))
      (node (ref "R1_PWRUSB") (pin "1") (pinfunction "1_1") (pintype "passive"))
      (node (ref "R2") (pin "1") (pinfunction "1_1") (pintype "passive"))
      (node (ref "R2-USB") (pin "2") (pinfunction "2_2") (pintype "passive"))
      (node (ref "R2-USB1") (pin "1") (pinfunction "1_1") (pintype "passive"))
      (node (ref "R2_BAT") (pin "1") (pinfunction "1_1") (pintype "passive"))
      (node (ref "R4") (pin "1") (pinfunction "1_1") (pintype "passive"))
      (node (ref "RESET_BUTTON") (pin "1") (pinfunction "1_1") (pintype "passive"))
      (node (ref "RESET_BUTTON") (pin "2") (pinfunction "2_2") (pintype "passive"))
      (node (ref "SENSOR2") (pin "1") (pinfunction "GND_1") (pintype "power_in"))
      (node (ref "SENSOR2") (pin "5") (pinfunction "SDO_5") (pintype "bidirectional"))
      (node (ref "SENSOR2") (pin "7") (pinfunction "GND_7") (pintype "power_in"))
      (node (ref "SJ1") (pin "1") (pinfunction "1_1") (pintype "passive"))
      (node (ref "U1") (pin "4") (pinfunction "GND_4") (pintype "power_in"))
      (node (ref "U1") (pin "9") (pinfunction "EXP_9") (pintype "passive"))
      (node (ref "U2") (pin "1") (pinfunction "GND_1") (pintype "power_in"))
      (node (ref "U2") (pin "28") (pinfunction "GND_28") (pintype "power_in"))
      (node (ref "U2") (pin "29_1") (pinfunction "GND_29_1") (pintype "power_in"))
      (node (ref "U2") (pin "29_2") (pinfunction "GND_29_2") (pintype "power_in"))
      (node (ref "U2") (pin "29_3") (pinfunction "GND_29_3") (pintype "power_in"))
      (node (ref "U2") (pin "29_4") (pinfunction "GND_29_4") (pintype "power_in"))
      (node (ref "U2") (pin "29_5") (pinfunction "GND_29_5") (pintype "power_in"))
      (node (ref "U2") (pin "29_6") (pinfunction "GND_29_6") (pintype "power_in"))
      (node (ref "U2") (pin "29_7") (pinfunction "GND_29_7") (pintype "power_in"))
      (node (ref "U2") (pin "29_8") (pinfunction "GND_29_8") (pintype "power_in"))
      (node (ref "U2") (pin "29_9") (pinfunction "GND_29_9") (pintype "power_in"))
      (node (ref "U3") (pin "13") (pinfunction "GND_13") (pintype "power_in"))
      (node (ref "U4") (pin "1") (pinfunction "CTG_1") (pintype "power_in"))
      (node (ref "U4") (pin "4") (pinfunction "GND_4") (pintype "power_in"))
      (node (ref "U4") (pin "6") (pinfunction "QSTRT_6") (pintype "input"))
      (node (ref "U4") (pin "9") (pinfunction "EP_9") (pintype "power_in"))
      (node (ref "U5") (pin "2") (pinfunction "VSS_2") (pintype "power_in"))
    )
    (net (code "15") (name "GPIOB") (class "Default")
      (node (ref "R1") (pin "1") (pinfunction "1_1") (pintype "passive"))
      (node (ref "U2") (pin "10") (pinfunction "IO8_10") (pintype "bidirectional"))
    )
    (net (code "16") (name "I2C_PW") (class "Default")
      (node (ref "U2") (pin "17") (pinfunction "IO19_17") (pintype "bidirectional"))
    )
    (net (code "17") (name "INT_RTC") (class "Default")
      (node (ref "R1_PINH1") (pin "1") (pinfunction "1_1") (pintype "passive"))
      (node (ref "TP15") (pin "TP") (pinfunction "TP_TP") (pintype "input"))
      (node (ref "U2") (pin "8") (pinfunction "IO0_8") (pintype "bidirectional"))
      (node (ref "U3") (pin "3") (pinfunction "SQW/~{INT}_3") (pintype "output"))
    )
    (net (code "18") (name "IO{slash}BOOT") (class "Default")
      (node (ref "BOOT_BUTTON") (pin "3") (pinfunction "3_3") (pintype "passive"))
      (node (ref "BOOT_BUTTON") (pin "4") (pinfunction "4_4") (pintype "passive"))
      (node (ref "C6") (pin "1") (pinfunction "1_1") (pintype "passive"))
      (node (ref "R_BOOT") (pin "1") (pinfunction "1_1") (pintype "passive"))
      (node (ref "U2") (pin "15") (pinfunction "IO9_15") (pintype "bidirectional"))
    )
    (net (code "19") (name "IO{slash}CHANGE") (class "Default")
      (node (ref "C10") (pin "1") (pinfunction "1_1") (pintype "passive"))
      (node (ref "CHANGE_BUTTON") (pin "3") (pinfunction "3_3") (pintype "passive"))
      (node (ref "CHANGE_BUTTON") (pin "4") (pinfunction "4_4") (pintype "passive"))
      (node (ref "R_CHANGE") (pin "1") (pinfunction "1_1") (pintype "passive"))
      (node (ref "U2") (pin "23") (pinfunction "IO15_23") (pintype "bidirectional"))
    )
    (net (code "20") (name "MISO") (class "Default")
      (node (ref "D12") (pin "2") (pinfunction "2_2") (pintype "passive"))
      (node (ref "J4") (pin "P7") (pinfunction "DAT0_P7") (pintype "bidirectional"))
      (node (ref "MISO") (pin "TP") (pinfunction "TP_TP") (pintype "input"))
      (node (ref "R8") (pin "1") (pinfunction "1_1") (pintype "passive"))
      (node (ref "U2") (pin "27") (pinfunction "IO2_27") (pintype "bidirectional"))
    )
    (net (code "21") (name "MOSI") (class "Default")
      (node (ref "D11") (pin "2") (pinfunction "2_2") (pintype "passive"))
      (node (ref "J1") (pin "14") (pinfunction "14_14") (pintype "bidirectional"))
      (node (ref "J4") (pin "P3") (pinfunction "CMD_P3") (pintype "bidirectional"))
      (node (ref "MOSI") (pin "TP") (pinfunction "TP_TP") (pintype "input"))
      (node (ref "R7") (pin "1") (pinfunction "1_1") (pintype "passive"))
      (node (ref "U1") (pin "5") (pinfunction "DI(IO0)_5") (pintype "bidirectional"))
      (node (ref "U2") (pin "7") (pinfunction "IO7_7") (pintype "bidirectional"))
    )
    (net (code "22") (name "Net-(CHG_LED-PadC)") (class "Default")
      (node (ref "CHG_LED") (pin "C") (pinfunction "C_C") (pintype "passive"))
      (node (ref "R1_BAT") (pin "1") (pinfunction "1_1") (pintype "passive"))
    )
    (net (code "23") (name "Net-(D2-CATHODE)") (class "Default")
      (node (ref "C1_BAT1") (pin "1") (pinfunction "1_1") (pintype "passive"))
      (node (ref "D2") (pin "1") (pinfunction "CATHODE_1") (pintype "bidirectional"))
      (node (ref "IC4") (pin "1") (pinfunction "VIN_1") (pintype "bidirectional"))
      (node (ref "IC4") (pin "3") (pinfunction "CE_3") (pintype "bidirectional"))
    )
    (net (code "24") (name "Net-(D3-A)") (class "Default")
      (node (ref "C4") (pin "1") (pinfunction "1_1") (pintype "passive"))
      (node (ref "D3") (pin "2") (pinfunction "A_2") (pintype "bidirectional"))
      (node (ref "D4") (pin "1") (pinfunction "K_1") (pintype "bidirectional"))
    )
    (net (code "25") (name "Net-(D7-CATHODE)") (class "Default")
      (node (ref "D7") (pin "1") (pinfunction "CATHODE_1") (pintype "bidirectional"))
      (node (ref "R_CAPACITOR") (pin "1") (pinfunction "1_1") (pintype "passive"))
    )
    (net (code "26") (name "Net-(EPD_C1-Pad2)") (class "Default")
      (node (ref "EPD_C1") (pin "2") (pinfunction "2_2") (pintype "passive"))
      (node (ref "J1") (pin "4") (pinfunction "4_4") (pintype "bidirectional"))
    )
    (net (code "27") (name "Net-(EPD_C2-Pad2)") (class "Default")
      (node (ref "EPD_C2") (pin "2") (pinfunction "2_2") (pintype "passive"))
      (node (ref "J1") (pin "5") (pinfunction "5_5") (pintype "bidirectional"))
    )
    (net (code "28") (name "Net-(EPD_C6-Pad2)") (class "Default")
      (node (ref "EPD_C6") (pin "2") (pinfunction "2_2") (pintype "passive"))
      (node (ref "J1") (pin "18") (pinfunction "18_18") (pintype "bidirectional"))
    )
    (net (code "29") (name "Net-(EPD_C7-Pad2)") (class "Default")
      (node (ref "EPD_C7") (pin "2") (pinfunction "2_2") (pintype "passive"))
      (node (ref "J1") (pin "19") (pinfunction "19_19") (pintype "bidirectional"))
    )
    (net (code "30") (name "Net-(EPD_C8-Pad2)") (class "Default")
      (node (ref "EPD_C8") (pin "2") (pinfunction "2_2") (pintype "passive"))
      (node (ref "J1") (pin "20") (pinfunction "20_20") (pintype "bidirectional"))
    )
    (net (code "31") (name "Net-(EPD_C10-Pad2)") (class "Default")
      (node (ref "EPD_C10") (pin "2") (pinfunction "2_2") (pintype "passive"))
      (node (ref "J1") (pin "22") (pinfunction "22_22") (pintype "bidirectional"))
    )
    (net (code "32") (name "Net-(EPD_C12-Pad2)") (class "Default")
      (node (ref "EPD_C12") (pin "2") (pinfunction "2_2") (pintype "passive"))
      (node (ref "J1") (pin "24") (pinfunction "24_24") (pintype "bidirectional"))
    )
    (net (code "33") (name "Net-(IC1-CT)") (class "Default")
      (node (ref "C_DELAY") (pin "1") (pinfunction "1_1") (pintype "passive"))
      (node (ref "IC1") (pin "5") (pinfunction "CT_5") (pintype "bidirectional"))
    )
    (net (code "34") (name "Net-(J2-PadA5)") (class "Default")
      (node (ref "J2") (pin "A5") (pinfunction "A5_A5") (pintype "bidirectional"))
      (node (ref "R2-USB1") (pin "2") (pinfunction "2_2") (pintype "passive"))
    )
    (net (code "35") (name "Net-(J2-PadB5)") (class "Default")
      (node (ref "J2") (pin "B5") (pinfunction "B5_B5") (pintype "bidirectional"))
      (node (ref "R2-USB") (pin "1") (pinfunction "1_1") (pintype "passive"))
    )
    (net (code "36") (name "Net-(U5-PROG)") (class "Default")
      (node (ref "R2_BAT") (pin "2") (pinfunction "2_2") (pintype "passive"))
      (node (ref "U5") (pin "5") (pinfunction "PROG_5") (pintype "input"))
    )
    (net (code "37") (name "Net-(U5-STAT)") (class "Default")
      (node (ref "R1_BAT") (pin "2") (pinfunction "2_2") (pintype "passive"))
      (node (ref "U5") (pin "1") (pinfunction "STAT_1") (pintype "output"))
    )
    (net (code "38") (name "PREVGH") (class "Default")
      (node (ref "D5") (pin "1") (pinfunction "K_1") (pintype "bidirectional"))
      (node (ref "EPD_C9") (pin "2") (pinfunction "2_2") (pintype "passive"))
      (node (ref "J1") (pin "21") (pinfunction "21_21") (pintype "bidirectional"))
    )
    (net (code "39") (name "PREVGL") (class "Default")
      (node (ref "D4") (pin "2") (pinfunction "A_2") (pintype "bidirectional"))
      (node (ref "EPD_C11") (pin "2") (pinfunction "2_2") (pintype "passive"))
      (node (ref "J1") (pin "23") (pinfunction "23_23") (pintype "bidirectional"))
    )
    (net (code "40") (name "RESE") (class "Default")
      (node (ref "J1") (pin "3") (pinfunction "3_3") (pintype "bidirectional"))
      (node (ref "Q3") (pin "2") (pinfunction "S_2") (pintype "bidirectional"))
      (node (ref "R3") (pin "2") (pinfunction "2_2") (pintype "passive"))
    )
    (net (code "41") (name "RESE'") (class "Default")
      (node (ref "R2") (pin "2") (pinfunction "2_2") (pintype "passive"))
      (node (ref "R3") (pin "1") (pinfunction "1_1") (pintype "passive"))
      (node (ref "SJ1") (pin "2") (pinfunction "2_2") (pintype "passive"))
    )
    (net (code "42") (name "RESET") (class "Default")
      (node (ref "C5") (pin "1") (pinfunction "1_1") (pintype "passive"))
      (node (ref "IC1") (pin "1") (pinfunction "VOUT_1") (pintype "bidirectional"))
      (node (ref "RESET_BUTTON") (pin "3") (pinfunction "3_3") (pintype "passive"))
      (node (ref "RESET_BUTTON") (pin "4") (pinfunction "4_4") (pintype "passive"))
      (node (ref "R_RESET") (pin "1") (pinfunction "1_1") (pintype "passive"))
      (node (ref "U2") (pin "3") (pinfunction "EN_3") (pintype "input"))
    )
    (net (code "43") (name "RTC_RST") (class "Default")
      (node (ref "U2") (pin "16") (pinfunction "IO18_16") (pintype "bidirectional"))
      (node (ref "U3") (pin "4") (pinfunction "~{RST}_4") (pintype "input"))
    )
    (net (code "44") (name "RX") (class "Default")
      (node (ref "RX") (pin "TP") (pinfunction "TP_TP") (pintype "input"))
      (node (ref "U2") (pin "24") (pinfunction "RXD0/GPIO17_24") (pintype "bidirectional"))
    )
    (net (code "45") (name "SCK") (class "Default")
      (node (ref "D10") (pin "2") (pinfunction "2_2") (pintype "passive"))
      (node (ref "J1") (pin "13") (pinfunction "13_13") (pintype "bidirectional"))
      (node (ref "J4") (pin "P5") (pinfunction "CLK_P5") (pintype "bidirectional"))
      (node (ref "R6") (pin "1") (pinfunction "1_1") (pintype "passive"))
      (node (ref "SCK") (pin "TP") (pinfunction "TP_TP") (pintype "input"))
      (node (ref "U1") (pin "6") (pinfunction "CLK_6") (pintype "input"))
      (node (ref "U2") (pin "6") (pinfunction "IO6_6") (pintype "bidirectional"))
    )
    (net (code "46") (name "SCL") (class "Default")
      (node (ref "J3") (pin "4") (pinfunction "4_4") (pintype "passive"))
      (node (ref "R2-PINH") (pin "1") (pinfunction "1_1") (pintype "passive"))
      (node (ref "SENSOR2") (pin "4") (pinfunction "SCK_4") (pintype "input"))
      (node (ref "U2") (pin "20") (pinfunction "IO22_20") (pintype "bidirectional"))
      (node (ref "U3") (pin "16") (pinfunction "SCL_16") (pintype "input"))
      (node (ref "U4") (pin "7") (pinfunction "SCL_7") (pintype "input"))
    )
    (net (code "47") (name "SDA") (class "Default")
      (node (ref "J3") (pin "3") (pinfunction "3_3") (pintype "passive"))
      (node (ref "R1_PINH") (pin "1") (pinfunction "1_1") (pintype "passive"))
      (node (ref "SENSOR2") (pin "3") (pinfunction "SDI_3") (pintype "bidirectional"))
      (node (ref "U2") (pin "19") (pinfunction "IO21_19") (pintype "bidirectional"))
      (node (ref "U3") (pin "15") (pinfunction "SDA_15") (pintype "bidirectional"))
      (node (ref "U4") (pin "8") (pinfunction "SDA_8") (pintype "bidirectional"))
    )
    (net (code "48") (name "SRC") (class "Default")
      (node (ref "C4") (pin "2") (pinfunction "2_2") (pintype "passive"))
      (node (ref "D5") (pin "2") (pinfunction "A_2") (pintype "bidirectional"))
      (node (ref "L1") (pin "1") (pinfunction "1_1") (pintype "passive"))
      (node (ref "Q3") (pin "3") (pinfunction "D_3") (pintype "bidirectional"))
    )
    (net (code "49") (name "SS_SD") (class "Default")
      (node (ref "D8") (pin "2") (pinfunction "2_2") (pintype "passive"))
      (node (ref "J4") (pin "P2") (pinfunction "CD/DAT3_P2") (pintype "bidirectional"))
      (node (ref "R10") (pin "1") (pinfunction "1_1") (pintype "passive"))
      (node (ref "U2") (pin "4") (pinfunction "IO4_4") (pintype "bidirectional"))
    )
    (net (code "50") (name "TX") (class "Default")
      (node (ref "TX") (pin "TP") (pinfunction "TP_TP") (pintype "input"))
      (node (ref "U2") (pin "25") (pinfunction "TXD0/GPIO16_25") (pintype "bidirectional"))
    )
    (net (code "51") (name "USB_D+") (class "Default")
      (node (ref "D1") (pin "1") (pinfunction "I/O1_1_1") (pintype "bidirectional"))
      (node (ref "U2") (pin "14") (pinfunction "IO13_14") (pintype "bidirectional"))
    )
    (net (code "52") (name "USB_D-") (class "Default")
      (node (ref "D1") (pin "3") (pinfunction "I/O2_1_3") (pintype "bidirectional"))
      (node (ref "U2") (pin "13") (pinfunction "IO12_13") (pintype "bidirectional"))
    )
    (net (code "53") (name "VBAT") (class "Default")
      (node (ref "C2_BAT") (pin "1") (pinfunction "1_1") (pintype "passive"))
      (node (ref "Q1") (pin "3") (pinfunction "D_3") (pintype "bidirectional"))
      (node (ref "U4") (pin "2") (pinfunction "CELL_2") (pintype "power_in"))
      (node (ref "U4") (pin "3") (pinfunction "VDD_3") (pintype "power_in"))
      (node (ref "U5") (pin "3") (pinfunction "VBAT_3") (pintype "power_in"))
      (node (ref "VBAT") (pin "TP") (pinfunction "TP_TP") (pintype "input"))
    )
    (net (code "54") (name "VBUS") (class "Default")
      (node (ref "C1_BAT") (pin "1") (pinfunction "1_1") (pintype "passive"))
      (node (ref "C4_USB") (pin "1") (pinfunction "1_1") (pintype "passive"))
      (node (ref "C5_USB") (pin "1") (pinfunction "1_1") (pintype "passive"))
      (node (ref "CHG_LED") (pin "A") (pinfunction "A_A") (pintype "passive"))
      (node (ref "D1") (pin "5") (pinfunction "VBUS_5") (pintype "bidirectional"))
      (node (ref "D2") (pin "2") (pinfunction "ANODE_2") (pintype "bidirectional"))
      (node (ref "PFMF.050.1") (pin "2") (pinfunction "2_2") (pintype "passive"))
      (node (ref "Q1") (pin "1") (pinfunction "G_1") (pintype "bidirectional"))
      (node (ref "R1_PWRUSB") (pin "2") (pinfunction "2_2") (pintype "passive"))
      (node (ref "TP14") (pin "TP") (pinfunction "TP_TP") (pintype "input"))
      (node (ref "U5") (pin "4") (pinfunction "VIN_4") (pintype "power_in"))
    )
    (net (code "55") (name "VRTC") (class "Default")
      (node (ref "C10_SUPERCAP") (pin "1") (pinfunction "1_1") (pintype "passive"))
      (node (ref "C8") (pin "1") (pinfunction "1_1") (pintype "passive"))
      (node (ref "R_CAPACITOR") (pin "2") (pinfunction "2_2") (pintype "passive"))
      (node (ref "U3") (pin "14") (pinfunction "VBAT_14") (pintype "power_in"))
    )
    (net (code "56") (name "VUSB") (class "Default")
      (node (ref "J2") (pin "A4") (pinfunction "A4_A4") (pintype "bidirectional"))
      (node (ref "J2") (pin "A9") (pinfunction "A9_A9") (pintype "bidirectional"))
      (node (ref "J2") (pin "B4") (pinfunction "B4_B4") (pintype "bidirectional"))
      (node (ref "J2") (pin "B9") (pinfunction "B9_B9") (pintype "bidirectional"))
      (node (ref "PFMF.050.1") (pin "1") (pinfunction "1_1") (pintype "passive"))
    )
    (net (code "57") (name "unconnected-(IC1-NC-Pad4)") (class "Default")
      (node (ref "IC1") (pin "4") (pinfunction "NC_4") (pintype "no_connect"))
    )
    (net (code "58") (name "unconnected-(IC4-NC-Pad4)") (class "Default")
      (node (ref "IC4") (pin "4") (pinfunction "NC_4") (pintype "no_connect"))
    )
    (net (code "59") (name "unconnected-(J1-Pad1)") (class "Default")
      (node (ref "J1") (pin "1") (pinfunction "1_1") (pintype "bidirectional"))
    )
    (net (code "60") (name "unconnected-(J1-Pad6)") (class "Default")
      (node (ref "J1") (pin "6") (pinfunction "6_6") (pintype "bidirectional"))
    )
    (net (code "61") (name "unconnected-(J1-Pad7)") (class "Default")
      (node (ref "J1") (pin "7") (pinfunction "7_7") (pintype "bidirectional"))
    )
    (net (code "62") (name "unconnected-(J2-PadA8)") (class "Default")
      (node (ref "J2") (pin "A8") (pinfunction "A8_A8") (pintype "bidirectional"))
    )
    (net (code "63") (name "unconnected-(J2-PadB8)") (class "Default")
      (node (ref "J2") (pin "B8") (pinfunction "B8_B8") (pintype "bidirectional"))
    )
    (net (code "64") (name "unconnected-(J4-DAT1-PadP8)") (class "Default")
      (node (ref "J4") (pin "P8") (pinfunction "DAT1_P8") (pintype "bidirectional"))
    )
    (net (code "65") (name "unconnected-(J4-DAT2-PadP1)") (class "Default")
      (node (ref "J4") (pin "P1") (pinfunction "DAT2_P1") (pintype "bidirectional"))
    )
    (net (code "66") (name "unconnected-(J4-DETECTION_1-PadS1)") (class "Default")
      (node (ref "J4") (pin "S1") (pinfunction "DETECTION_1_S1") (pintype "bidirectional"))
    )
    (net (code "67") (name "unconnected-(J4-DETECTION_2-PadS2)") (class "Default")
      (node (ref "J4") (pin "S2") (pinfunction "DETECTION_2_S2") (pintype "bidirectional"))
    )
    (net (code "68") (name "unconnected-(Q1-S-Pad2)") (class "Default")
      (node (ref "Q1") (pin "2") (pinfunction "S_2") (pintype "bidirectional"))
    )
    (net (code "69") (name "unconnected-(U1-DO(IO1)-Pad2)") (class "Default")
      (node (ref "U1") (pin "2") (pinfunction "DO(IO1)_2") (pintype "bidirectional"))
    )
    (net (code "70") (name "unconnected-(U2-NC-Pad22)") (class "Default")
      (node (ref "U2") (pin "22") (pinfunction "NC_22") (pintype "no_connect"))
    )
    (net (code "71") (name "unconnected-(U4-~{ALERT}-Pad5)") (class "Default")
      (node (ref "U4") (pin "5") (pinfunction "~{ALERT}_5") (pintype "output"))
    )
  )
)
